# OKUMU-JIMMY-WORK-MODULE_2025-07-22.net
KiCad netlist of a schematic drawn in EasyEDA
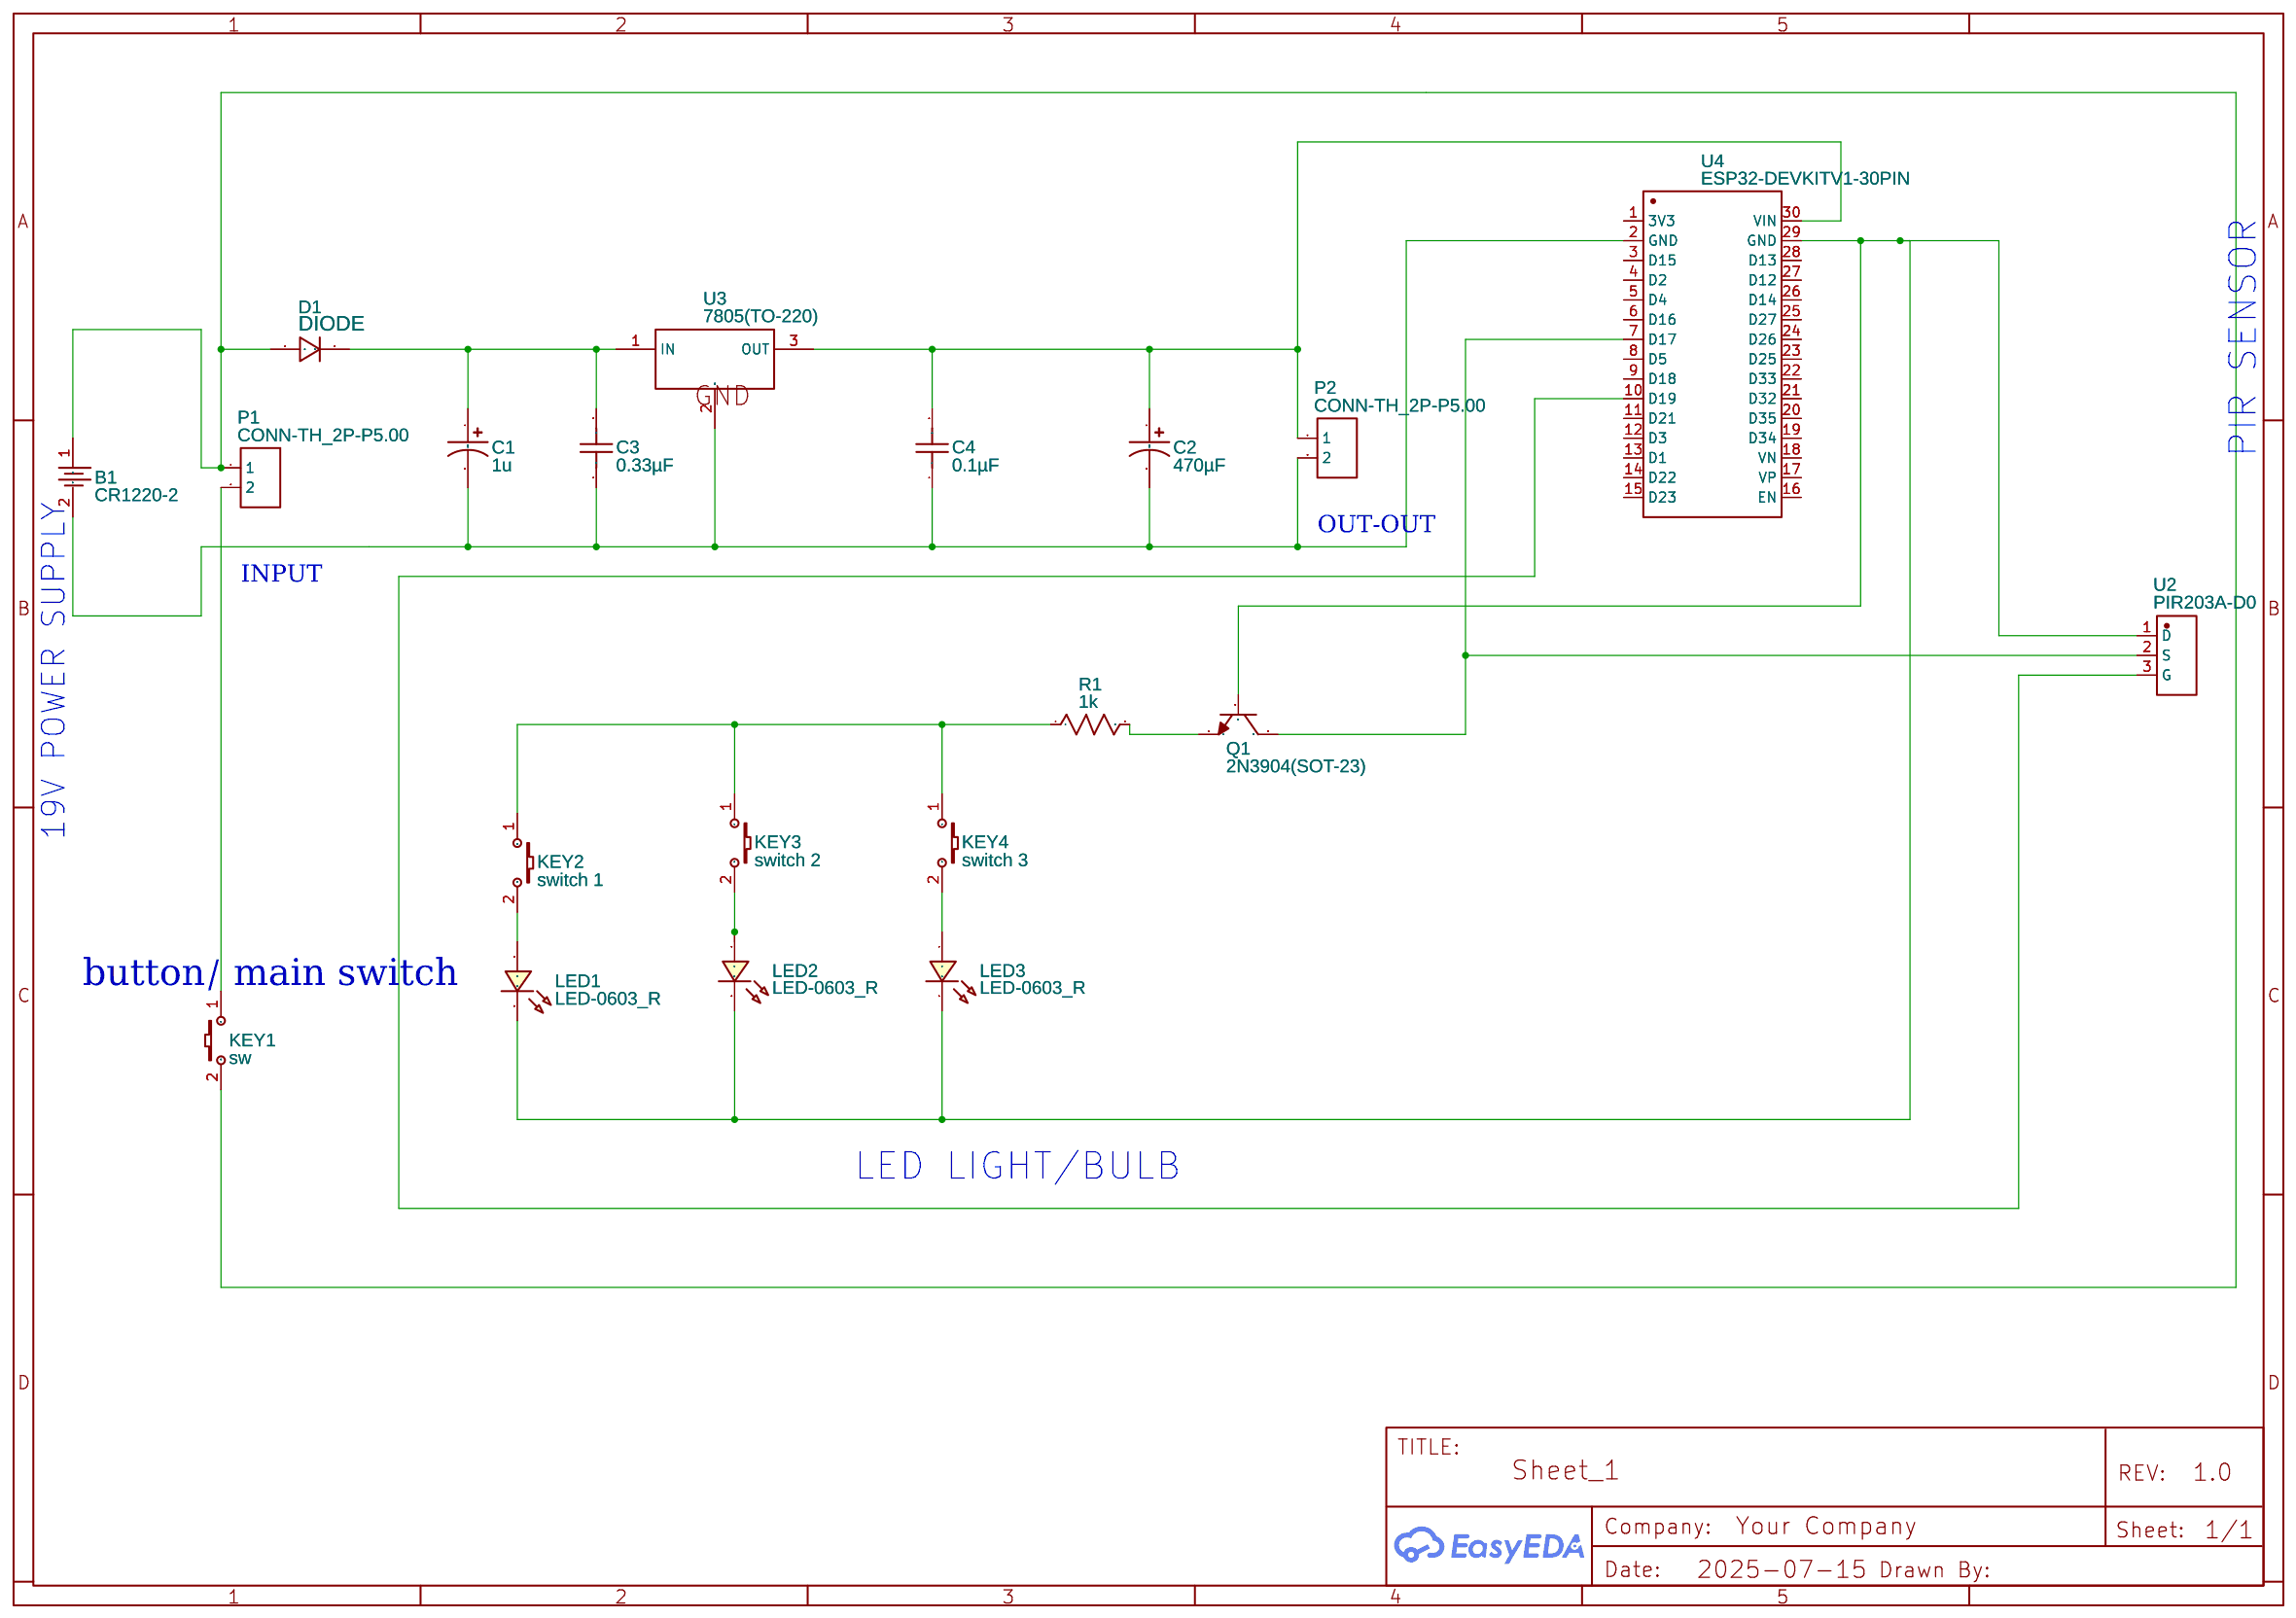
[diagram p0: schematic sheet]

(export (version "E")
  (design (tool "Eeschema 10.0.6"))
  (components
    (comp (ref "B1")
      (value "CR1220-2")
      (fields (field (name "Manufacturer") "Q&J"))
      (libsource (lib "") (part "CR1220-2"))
    )
    (comp (ref "C1") (value "1u") (libsource (lib "") (part "CE_TH_D3.0×F1.5_US")))
    (comp (ref "C2") (value "470µF") (libsource (lib "") (part "CE_TH_D3.0×F1.5_US")))
    (comp (ref "C3") (value "0.33µF") (libsource (lib "") (part "C_RAD-0.1_US")))
    (comp (ref "C4") (value "0.1µF") (libsource (lib "") (part "C_RAD-0.1_US")))
    (comp (ref "D1")
      (value "DIODE")
      (fields (field (name "Manufacturer Part") "1N4007W") (field (name "Manufacturer") "BLUE ROCKET"))
      (libsource (lib "") (part "1N4007W"))
    )
    (comp (ref "KEY1")
      (value "sw")
      (fields (field (name "Manufacturer Part") "K2-1107ST-A4SW-06"))
      (libsource (lib "") (part "K2-3.6×6.1_SMD_1"))
    )
    (comp (ref "KEY2")
      (value "switch 1")
      (fields (field (name "Manufacturer Part") "K2-1107ST-A4SW-06"))
      (libsource (lib "") (part "K2-3.6×6.1_SMD"))
    )
    (comp (ref "KEY3")
      (value "switch 2")
      (fields (field (name "Manufacturer Part") "K2-1107ST-A4SW-06"))
      (libsource (lib "") (part "K2-3.6×6.1_SMD"))
    )
    (comp (ref "KEY4")
      (value "switch 3")
      (fields (field (name "Manufacturer Part") "K2-1107ST-A4SW-06"))
      (libsource (lib "") (part "K2-3.6×6.1_SMD"))
    )
    (comp (ref "LED1")
      (value "LED-0603_R")
      (fields
        (field (name "Manufacturer Part") "19-217/R6C-AL1M2VY/3T")
        (field (name "Manufacturer") "EVERLIGHT(台湾亿光)")
      )
      (libsource (lib "") (part "LED-0603_R"))
    )
    (comp (ref "LED2")
      (value "LED-0603_R")
      (fields
        (field (name "Manufacturer Part") "19-217/R6C-AL1M2VY/3T")
        (field (name "Manufacturer") "EVERLIGHT(台湾亿光)")
      )
      (libsource (lib "") (part "LED-0603_R"))
    )
    (comp (ref "LED3")
      (value "LED-0603_R")
      (fields
        (field (name "Manufacturer Part") "19-217/R6C-AL1M2VY/3T")
        (field (name "Manufacturer") "EVERLIGHT(台湾亿光)")
      )
      (libsource (lib "") (part "LED-0603_R"))
    )
    (comp (ref "P1") (value "CONN-TH_2P-P5.00") (libsource (lib "") (part "CONN-TH_2P-P5.00")))
    (comp (ref "P2") (value "CONN-TH_2P-P5.00") (libsource (lib "") (part "CONN-TH_2P-P5.00")))
    (comp (ref "Q1")
      (value "2N3904(SOT-23)")
      (fields (field (name "Manufacturer Part") "2n3904S-RTK/PS") (field (name "Manufacturer") "KEC"))
      (libsource (lib "") (part "2N3904(SOT-23)"))
    )
    (comp (ref "R1") (value "1k") (libsource (lib "") (part "R_0603_US")))
    (comp (ref "U2")
      (value "PIR203A-D0")
      (fields (field (name "Manufacturer") "NEWOPTO(鑫永诚光电)"))
      (libsource (lib "") (part "PIR203A-D0"))
    )
    (comp (ref "U3")
      (value "7805(TO-220)")
      (fields
        (field (name "Manufacturer Part") "L7805CV-DG")
        (field (name "Manufacturer") "STMicroelectronics")
      )
      (libsource (lib "") (part "7805(TO-220)"))
    )
    (comp (ref "U4")
      (value "ESP32-DEVKITV1-30PIN")
      (fields
        (field (name "Manufacturer Part") "ESP32-DevKitV")
        (field (name "Manufacturer") "ESPRESSIF(乐鑫)")
      )
      (libsource (lib "") (part "ESP32-DEVKITV1-30PIN"))
    )
  )
  (nets
    (net (code "1") (name "Net-(B1-Pad1)") (class "Default")
      (node (ref "B1") (pin "1") (pinfunction "1_1") (pintype "input"))
      (node (ref "D1") (pin "2") (pinfunction "2_2") (pintype "unspecified"))
      (node (ref "KEY1") (pin "2") (pinfunction "2_2") (pintype "unspecified"))
      (node (ref "P1") (pin "1") (pinfunction "1_1") (pintype "unspecified"))
    )
    (net (code "2") (name "Net-(KEY1-Pad1)") (class "Default")
      (node (ref "KEY1") (pin "1") (pinfunction "1_1") (pintype "unspecified"))
      (node (ref "P1") (pin "2") (pinfunction "2_2") (pintype "unspecified"))
    )
    (net (code "3") (name "Net-(KEY2-Pad1)") (class "Default")
      (node (ref "KEY2") (pin "1") (pinfunction "1_1") (pintype "unspecified"))
      (node (ref "KEY3") (pin "1") (pinfunction "1_1") (pintype "unspecified"))
      (node (ref "KEY4") (pin "1") (pinfunction "1_1") (pintype "unspecified"))
      (node (ref "R1") (pin "1") (pinfunction "1_1") (pintype "unspecified"))
    )
    (net (code "4") (name "Net-(KEY2-Pad2)") (class "Default")
      (node (ref "KEY2") (pin "2") (pinfunction "2_2") (pintype "unspecified"))
      (node (ref "LED1") (pin "1") (pinfunction "1_1") (pintype "unspecified"))
    )
    (net (code "5") (name "Net-(KEY3-Pad2)") (class "Default")
      (node (ref "KEY3") (pin "2") (pinfunction "2_2") (pintype "unspecified"))
      (node (ref "LED2") (pin "1") (pinfunction "1_1") (pintype "unspecified"))
    )
    (net (code "6") (name "Net-(KEY4-Pad2)") (class "Default")
      (node (ref "KEY4") (pin "2") (pinfunction "2_2") (pintype "unspecified"))
      (node (ref "LED3") (pin "1") (pinfunction "1_1") (pintype "unspecified"))
    )
    (net (code "7") (name "Net-(Q1-B)") (class "Default")
      (node (ref "LED1") (pin "2") (pinfunction "2_2") (pintype "unspecified"))
      (node (ref "LED2") (pin "2") (pinfunction "2_2") (pintype "unspecified"))
      (node (ref "LED3") (pin "2") (pinfunction "2_2") (pintype "unspecified"))
      (node (ref "Q1") (pin "2") (pinfunction "B_2") (pintype "input"))
      (node (ref "U2") (pin "1") (pinfunction "D_1") (pintype "unspecified"))
      (node (ref "U4") (pin "29") (pinfunction "GND_29") (pintype "unspecified"))
    )
    (net (code "8") (name "Net-(Q1-C)") (class "Default")
      (node (ref "Q1") (pin "3") (pinfunction "C_3") (pintype "input"))
      (node (ref "U2") (pin "2") (pinfunction "S_2") (pintype "unspecified"))
      (node (ref "U4") (pin "7") (pinfunction "D17_7") (pintype "unspecified"))
    )
    (net (code "9") (name "Net-(Q1-E)") (class "Default")
      (node (ref "Q1") (pin "1") (pinfunction "E_1") (pintype "input"))
      (node (ref "R1") (pin "2") (pinfunction "2_2") (pintype "unspecified"))
    )
    (net (code "10") (name "Net-(U2-G)") (class "Default")
      (node (ref "U2") (pin "3") (pinfunction "G_3") (pintype "unspecified"))
      (node (ref "U4") (pin "10") (pinfunction "D19_10") (pintype "unspecified"))
    )
    (net (code "11") (name "Net-(U3-GND)") (class "Default")
      (node (ref "B1") (pin "2") (pinfunction "2_2") (pintype "input"))
      (node (ref "C1") (pin "2") (pinfunction "2_2") (pintype "unspecified"))
      (node (ref "C2") (pin "2") (pinfunction "2_2") (pintype "unspecified"))
      (node (ref "C3") (pin "1") (pinfunction "1_1") (pintype "unspecified"))
      (node (ref "C4") (pin "1") (pinfunction "1_1") (pintype "unspecified"))
      (node (ref "P2") (pin "2") (pinfunction "2_2") (pintype "unspecified"))
      (node (ref "U3") (pin "2") (pinfunction "GND_2") (pintype "passive"))
      (node (ref "U4") (pin "2") (pinfunction "GND_2") (pintype "unspecified"))
    )
    (net (code "12") (name "Net-(U3-IN)") (class "Default")
      (node (ref "C1") (pin "1") (pinfunction "1_1") (pintype "unspecified"))
      (node (ref "C3") (pin "2") (pinfunction "2_2") (pintype "unspecified"))
      (node (ref "D1") (pin "1") (pinfunction "1_1") (pintype "unspecified"))
      (node (ref "U3") (pin "1") (pinfunction "IN_1") (pintype "passive"))
    )
    (net (code "13") (name "Net-(U3-OUT)") (class "Default")
      (node (ref "C2") (pin "1") (pinfunction "1_1") (pintype "unspecified"))
      (node (ref "C4") (pin "2") (pinfunction "2_2") (pintype "unspecified"))
      (node (ref "P2") (pin "1") (pinfunction "1_1") (pintype "unspecified"))
      (node (ref "U3") (pin "3") (pinfunction "OUT_3") (pintype "passive"))
      (node (ref "U4") (pin "30") (pinfunction "VIN_30") (pintype "unspecified"))
    )
    (net (code "14") (name "unconnected-(U4-3V3-Pad1)") (class "Default")
      (node (ref "U4") (pin "1") (pinfunction "3V3_1") (pintype "unspecified"))
    )
    (net (code "15") (name "unconnected-(U4-D1-Pad13)") (class "Default")
      (node (ref "U4") (pin "13") (pinfunction "D1_13") (pintype "unspecified"))
    )
    (net (code "16") (name "unconnected-(U4-D2-Pad4)") (class "Default")
      (node (ref "U4") (pin "4") (pinfunction "D2_4") (pintype "unspecified"))
    )
    (net (code "17") (name "unconnected-(U4-D3-Pad12)") (class "Default")
      (node (ref "U4") (pin "12") (pinfunction "D3_12") (pintype "unspecified"))
    )
    (net (code "18") (name "unconnected-(U4-D4-Pad5)") (class "Default")
      (node (ref "U4") (pin "5") (pinfunction "D4_5") (pintype "unspecified"))
    )
    (net (code "19") (name "unconnected-(U4-D5-Pad8)") (class "Default")
      (node (ref "U4") (pin "8") (pinfunction "D5_8") (pintype "unspecified"))
    )
    (net (code "20") (name "unconnected-(U4-D12-Pad27)") (class "Default")
      (node (ref "U4") (pin "27") (pinfunction "D12_27") (pintype "unspecified"))
    )
    (net (code "21") (name "unconnected-(U4-D13-Pad28)") (class "Default")
      (node (ref "U4") (pin "28") (pinfunction "D13_28") (pintype "unspecified"))
    )
    (net (code "22") (name "unconnected-(U4-D14-Pad26)") (class "Default")
      (node (ref "U4") (pin "26") (pinfunction "D14_26") (pintype "unspecified"))
    )
    (net (code "23") (name "unconnected-(U4-D15-Pad3)") (class "Default")
      (node (ref "U4") (pin "3") (pinfunction "D15_3") (pintype "unspecified"))
    )
    (net (code "24") (name "unconnected-(U4-D16-Pad6)") (class "Default")
      (node (ref "U4") (pin "6") (pinfunction "D16_6") (pintype "unspecified"))
    )
    (net (code "25") (name "unconnected-(U4-D18-Pad9)") (class "Default")
      (node (ref "U4") (pin "9") (pinfunction "D18_9") (pintype "unspecified"))
    )
    (net (code "26") (name "unconnected-(U4-D21-Pad11)") (class "Default")
      (node (ref "U4") (pin "11") (pinfunction "D21_11") (pintype "unspecified"))
    )
    (net (code "27") (name "unconnected-(U4-D22-Pad14)") (class "Default")
      (node (ref "U4") (pin "14") (pinfunction "D22_14") (pintype "unspecified"))
    )
    (net (code "28") (name "unconnected-(U4-D23-Pad15)") (class "Default")
      (node (ref "U4") (pin "15") (pinfunction "D23_15") (pintype "unspecified"))
    )
    (net (code "29") (name "unconnected-(U4-D25-Pad23)") (class "Default")
      (node (ref "U4") (pin "23") (pinfunction "D25_23") (pintype "unspecified"))
    )
    (net (code "30") (name "unconnected-(U4-D26-Pad24)") (class "Default")
      (node (ref "U4") (pin "24") (pinfunction "D26_24") (pintype "unspecified"))
    )
    (net (code "31") (name "unconnected-(U4-D27-Pad25)") (class "Default")
      (node (ref "U4") (pin "25") (pinfunction "D27_25") (pintype "unspecified"))
    )
    (net (code "32") (name "unconnected-(U4-D32-Pad21)") (class "Default")
      (node (ref "U4") (pin "21") (pinfunction "D32_21") (pintype "unspecified"))
    )
    (net (code "33") (name "unconnected-(U4-D33-Pad22)") (class "Default")
      (node (ref "U4") (pin "22") (pinfunction "D33_22") (pintype "unspecified"))
    )
    (net (code "34") (name "unconnected-(U4-D34-Pad19)") (class "Default")
      (node (ref "U4") (pin "19") (pinfunction "D34_19") (pintype "unspecified"))
    )
    (net (code "35") (name "unconnected-(U4-D35-Pad20)") (class "Default")
      (node (ref "U4") (pin "20") (pinfunction "D35_20") (pintype "unspecified"))
    )
    (net (code "36") (name "unconnected-(U4-EN-Pad16)") (class "Default")
      (node (ref "U4") (pin "16") (pinfunction "EN_16") (pintype "unspecified"))
    )
    (net (code "37") (name "unconnected-(U4-VN-Pad18)") (class "Default")
      (node (ref "U4") (pin "18") (pinfunction "VN_18") (pintype "unspecified"))
    )
    (net (code "38") (name "unconnected-(U4-VP-Pad17)") (class "Default")
      (node (ref "U4") (pin "17") (pinfunction "VP_17") (pintype "unspecified"))
    )
  )
)
